# DMESC.net
KiCad netlist of a schematic drawn in Altium Designer
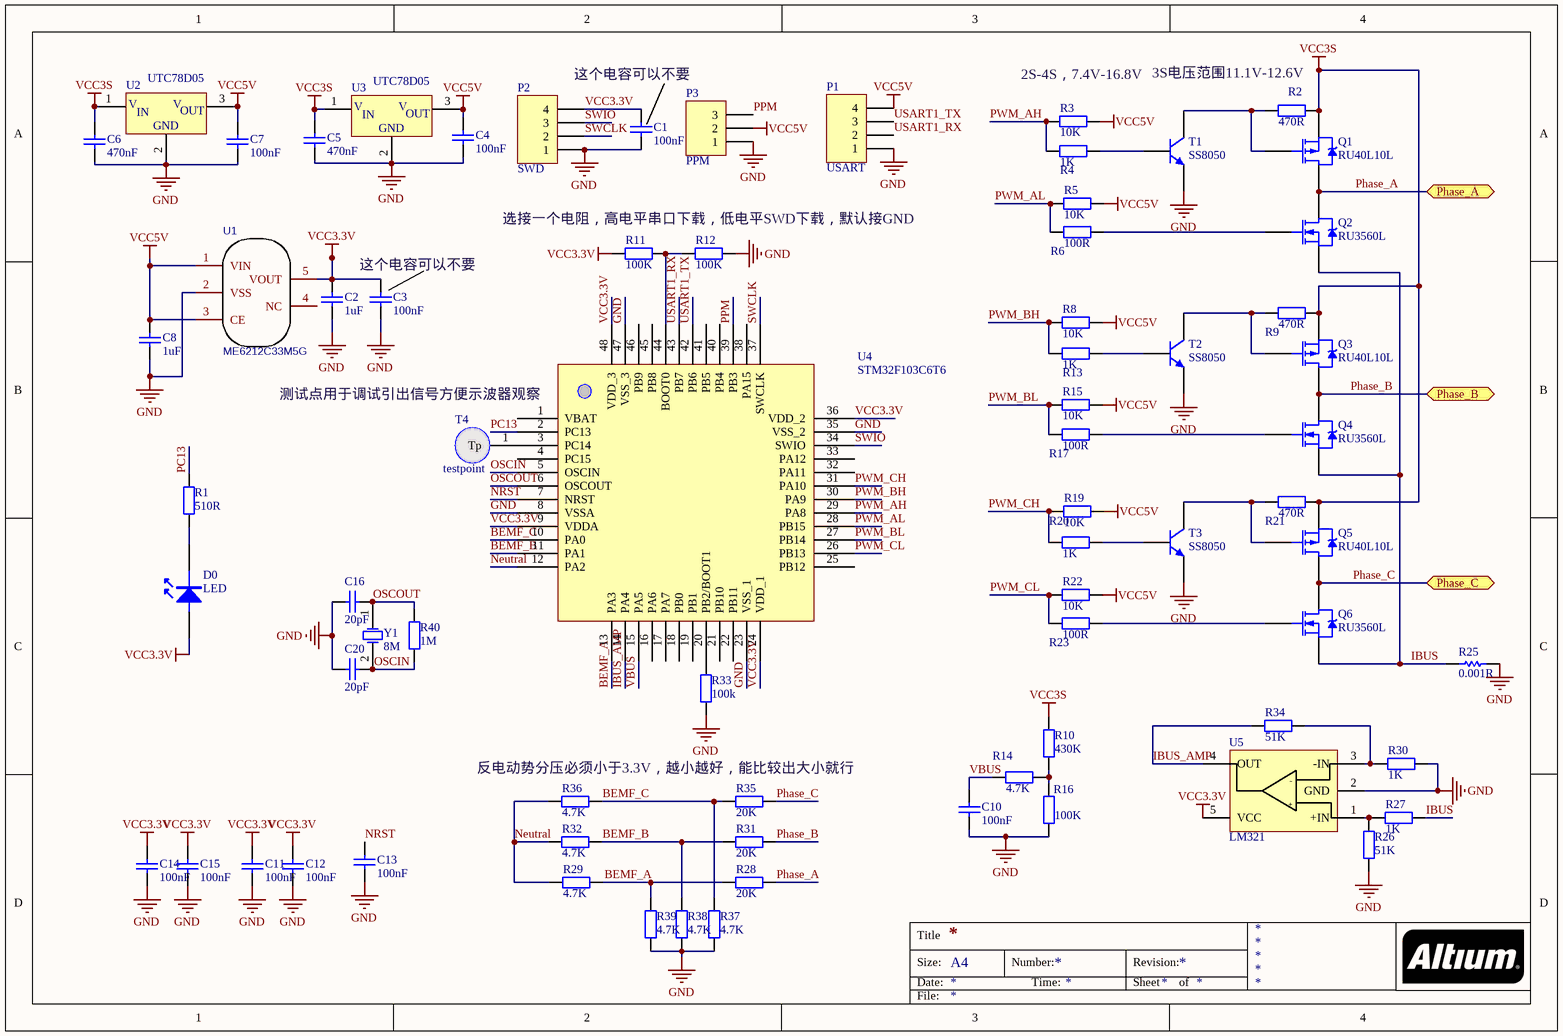
[diagram p0: DMESC.SchDoc]

(export (version "E")
  (design (tool "Eeschema 10.0.6"))
  (components
    (comp (ref "C1")
      (value "100nF")
      (footprint "C0603")
      (description "0.1uF")
      (fields (field (name "PUBLISHER") "Altium Limited"))
      (libsource (lib "Miscellaneous Devices") (part "Cap"))
    )
    (comp (ref "C2")
      (value "1uF")
      (footprint "C0603")
      (fields (field (name "PUBLISHER") "Altium Limited"))
      (libsource (lib "Miscellaneous Devices") (part "Cap"))
    )
    (comp (ref "C3")
      (value "100nF")
      (footprint "C0603")
      (description "0.1uF")
      (fields (field (name "PUBLISHER") "Altium Limited"))
      (libsource (lib "Miscellaneous Devices") (part "Cap"))
    )
    (comp (ref "C4")
      (value "100nF")
      (footprint "C0603")
      (description "贴片电容")
      (fields (field (name "PUBLISHER") "Altium Limited"))
      (libsource (lib "Miscellaneous Devices") (part "Cap"))
    )
    (comp (ref "C5")
      (value "470nF")
      (footprint "C0603")
      (description "贴片电容")
      (fields (field (name "PUBLISHER") "Altium Limited"))
      (libsource (lib "Miscellaneous Devices") (part "Cap"))
    )
    (comp (ref "C6")
      (value "470nF")
      (footprint "C0603")
      (description "贴片电容")
      (fields (field (name "PUBLISHER") "Altium Limited"))
      (libsource (lib "Miscellaneous Devices") (part "Cap"))
    )
    (comp (ref "C7")
      (value "100nF")
      (footprint "C0603")
      (description "贴片电容")
      (fields (field (name "PUBLISHER") "Altium Limited"))
      (libsource (lib "Miscellaneous Devices") (part "Cap"))
    )
    (comp (ref "C8")
      (value "1uF")
      (footprint "C0603")
      (fields (field (name "PUBLISHER") "Altium Limited"))
      (libsource (lib "Miscellaneous Devices") (part "Cap"))
    )
    (comp (ref "C10")
      (value "100nF")
      (footprint "C0603")
      (description "Capacitor")
      (fields (field (name "PUBLISHER") "Altium Limited"))
      (libsource (lib "Miscellaneous Devices") (part "Cap"))
    )
    (comp (ref "C11")
      (value "100nF")
      (footprint "C0603")
      (description "0.1uF")
      (fields (field (name "PUBLISHER") "Altium Limited"))
      (libsource (lib "Miscellaneous Devices") (part "Cap"))
    )
    (comp (ref "C12")
      (value "100nF")
      (footprint "C0603")
      (description "0.1uF")
      (fields (field (name "PUBLISHER") "Altium Limited"))
      (libsource (lib "Miscellaneous Devices") (part "Cap"))
    )
    (comp (ref "C13")
      (value "100nF")
      (footprint "C0603")
      (description "0.1uF")
      (fields (field (name "PUBLISHER") "Altium Limited"))
      (libsource (lib "Miscellaneous Devices") (part "Cap"))
    )
    (comp (ref "C14")
      (value "100nF")
      (footprint "C0603")
      (description "0.1uF")
      (fields (field (name "PUBLISHER") "Altium Limited"))
      (libsource (lib "Miscellaneous Devices") (part "Cap"))
    )
    (comp (ref "C15")
      (value "100nF")
      (footprint "C0603")
      (description "0.1uF")
      (fields (field (name "PUBLISHER") "Altium Limited"))
      (libsource (lib "Miscellaneous Devices") (part "Cap"))
    )
    (comp (ref "C16")
      (value "20pF")
      (footprint "C0603")
      (description "0603")
      (fields (field (name "PUBLISHER") "Altium Limited"))
      (libsource (lib "STM32F103C8T6") (part "Cap"))
    )
    (comp (ref "C20")
      (value "20pF")
      (footprint "C0603")
      (description "0603")
      (fields (field (name "PUBLISHER") "Altium Limited"))
      (libsource (lib "STM32F103C8T6") (part "Cap"))
    )
    (comp (ref "D0") (value "LED") (footprint "0603LED") (libsource (lib "DMESC_1") (part "LED")))
    (comp (ref "P1")
      (value "USART")
      (footprint "HDR1X4")
      (description "Header, 4-Pin")
      (fields (field (name "PUBLISHER") "Altium Limited"))
      (libsource (lib "Miscellaneous Connectors") (part "Header 4"))
    )
    (comp (ref "P2")
      (value "SWD")
      (footprint "HDR1X4")
      (description "Header, 4-Pin")
      (fields (field (name "PUBLISHER") "Altium Limited"))
      (libsource (lib "STM32F103C8T6") (part "Header 4"))
    )
    (comp (ref "P3")
      (value "PPM")
      (footprint "HDR1X3")
      (description "Header, 3-Pin")
      (fields (field (name "PUBLISHER") "Altium Limited"))
      (libsource (lib "Miscellaneous Connectors") (part "Header 3"))
    )
    (comp (ref "Q1")
      (value "RU40L10L")
      (footprint "TO-252")
      (description "PMOSFET")
      (fields
        (field (name "MANUFACTURER") "International Rectifier")
        (field (name "PUBLISHER") "Altium Limited")
      )
      (libsource (lib "DMESC_1") (part "IRFR5305"))
    )
    (comp (ref "Q2")
      (value "RU3560L")
      (footprint "TO-252")
      (description "NMOSFET")
      (fields
        (field (name "MANUFACTURER") "International Rectifier")
        (field (name "PUBLISHER") "Altium Limited")
      )
      (libsource (lib "DMESC_1") (part "IRFR1205"))
    )
    (comp (ref "Q3")
      (value "RU40L10L")
      (footprint "TO-252")
      (description "PMOSFET")
      (fields
        (field (name "MANUFACTURER") "International Rectifier")
        (field (name "PUBLISHER") "Altium Limited")
      )
      (libsource (lib "DMESC_1") (part "IRFR5305"))
    )
    (comp (ref "Q4")
      (value "RU3560L")
      (footprint "TO-252")
      (description "NMOSFET")
      (fields
        (field (name "MANUFACTURER") "International Rectifier")
        (field (name "PUBLISHER") "Altium Limited")
      )
      (libsource (lib "DMESC_1") (part "IRFR1205"))
    )
    (comp (ref "Q5")
      (value "RU40L10L")
      (footprint "TO-252")
      (description "PMOSFET")
      (fields
        (field (name "MANUFACTURER") "International Rectifier")
        (field (name "PUBLISHER") "Altium Limited")
      )
      (libsource (lib "DMESC_1") (part "IRFR5305"))
    )
    (comp (ref "Q6")
      (value "RU3560L")
      (footprint "TO-252")
      (description "NMOSFET")
      (fields
        (field (name "MANUFACTURER") "International Rectifier")
        (field (name "PUBLISHER") "Altium Limited")
      )
      (libsource (lib "DMESC_1") (part "IRFR1205"))
    )
    (comp (ref "R1")
      (value "510R")
      (footprint "R0603")
      (description "0603")
      (fields (field (name "PUBLISHER") "Altium Limited"))
      (libsource (lib "") (part "Res2_3"))
    )
    (comp (ref "R2")
      (value "470R")
      (footprint "R0603")
      (description "Resistor")
      (fields (field (name "PUBLISHER") "Altium Limited"))
      (libsource (lib "") (part "Res2_1"))
    )
    (comp (ref "R3")
      (value "10K")
      (footprint "R0603")
      (description "Resistor")
      (fields (field (name "PUBLISHER") "Altium Limited"))
      (libsource (lib "") (part "Res2_1"))
    )
    (comp (ref "R4")
      (value "1K")
      (footprint "R0603")
      (description "Resistor")
      (fields (field (name "PUBLISHER") "Altium Limited"))
      (libsource (lib "") (part "Res2_1"))
    )
    (comp (ref "R5")
      (value "10K")
      (footprint "R0603")
      (description "Resistor")
      (fields (field (name "PUBLISHER") "Altium Limited"))
      (libsource (lib "") (part "Res2_1"))
    )
    (comp (ref "R6")
      (value "100R")
      (footprint "R0603")
      (description "Resistor")
      (fields (field (name "PUBLISHER") "Altium Limited"))
      (libsource (lib "") (part "Res2_1"))
    )
    (comp (ref "R8")
      (value "10K")
      (footprint "R0603")
      (description "Resistor")
      (fields (field (name "PUBLISHER") "Altium Limited"))
      (libsource (lib "") (part "Res2_1"))
    )
    (comp (ref "R9")
      (value "470R")
      (footprint "R0603")
      (description "Resistor")
      (fields (field (name "PUBLISHER") "Altium Limited"))
      (libsource (lib "") (part "Res2_1"))
    )
    (comp (ref "R10")
      (value "430K")
      (footprint "R0603")
      (description "Resistor")
      (fields (field (name "PUBLISHER") "Altium Limited"))
      (libsource (lib "Miscellaneous Devices") (part "Res2"))
    )
    (comp (ref "R11")
      (value "100K")
      (footprint "R0603")
      (description "0603")
      (fields (field (name "PUBLISHER") "Altium Limited"))
      (libsource (lib "") (part "Res2_2"))
    )
    (comp (ref "R12")
      (value "100K")
      (footprint "R0603")
      (description "0603")
      (fields (field (name "PUBLISHER") "Altium Limited"))
      (libsource (lib "") (part "Res2_1"))
    )
    (comp (ref "R13")
      (value "1K")
      (footprint "R0603")
      (description "Resistor")
      (fields (field (name "PUBLISHER") "Altium Limited"))
      (libsource (lib "") (part "Res2_1"))
    )
    (comp (ref "R14")
      (value "4.7K")
      (footprint "R0603")
      (description "Resistor")
      (fields (field (name "PUBLISHER") "Altium Limited"))
      (libsource (lib "") (part "Res2_1"))
    )
    (comp (ref "R15")
      (value "10K")
      (footprint "R0603")
      (description "Resistor")
      (fields (field (name "PUBLISHER") "Altium Limited"))
      (libsource (lib "") (part "Res2_1"))
    )
    (comp (ref "R16")
      (value "100K")
      (footprint "R0603")
      (description "Resistor")
      (fields (field (name "PUBLISHER") "Altium Limited"))
      (libsource (lib "Miscellaneous Devices") (part "Res2"))
    )
    (comp (ref "R17")
      (value "100R")
      (footprint "R0603")
      (description "Resistor")
      (fields (field (name "PUBLISHER") "Altium Limited"))
      (libsource (lib "") (part "Res2_1"))
    )
    (comp (ref "R19")
      (value "10K")
      (footprint "R0603")
      (description "Resistor")
      (fields (field (name "PUBLISHER") "Altium Limited"))
      (libsource (lib "") (part "Res2_1"))
    )
    (comp (ref "R20")
      (value "1K")
      (footprint "R0603")
      (description "Resistor")
      (fields (field (name "PUBLISHER") "Altium Limited"))
      (libsource (lib "") (part "Res2_1"))
    )
    (comp (ref "R21")
      (value "470R")
      (footprint "R0603")
      (description "Resistor")
      (fields (field (name "PUBLISHER") "Altium Limited"))
      (libsource (lib "") (part "Res2_1"))
    )
    (comp (ref "R22")
      (value "10K")
      (footprint "R0603")
      (description "Resistor")
      (fields (field (name "PUBLISHER") "Altium Limited"))
      (libsource (lib "") (part "Res2_1"))
    )
    (comp (ref "R23")
      (value "100R")
      (footprint "R0603")
      (description "Resistor")
      (fields (field (name "PUBLISHER") "Altium Limited"))
      (libsource (lib "") (part "Res2_1"))
    )
    (comp (ref "R25")
      (value "0.001R")
      (footprint "2512")
      (description "11毫欧采样电阻")
      (fields (field (name "PUBLISHER") "Altium Limited"))
      (libsource (lib "Miscellaneous Devices") (part "Res1"))
    )
    (comp (ref "R26")
      (value "51K")
      (footprint "R0603")
      (description "Resistor")
      (fields (field (name "PUBLISHER") "Altium Limited"))
      (libsource (lib "") (part "Res2_3"))
    )
    (comp (ref "R27")
      (value "1K")
      (footprint "R0603")
      (description "Resistor")
      (fields (field (name "PUBLISHER") "Altium Limited"))
      (libsource (lib "") (part "Res2_2"))
    )
    (comp (ref "R28")
      (value "20K")
      (footprint "R0603")
      (description "Resistor")
      (fields (field (name "PUBLISHER") "Altium Limited"))
      (libsource (lib "") (part "Res2_2"))
    )
    (comp (ref "R29")
      (value "4.7K")
      (footprint "R0603")
      (description "Resistor")
      (fields (field (name "PUBLISHER") "Altium Limited"))
      (libsource (lib "") (part "Res2_2"))
    )
    (comp (ref "R30")
      (value "1K")
      (footprint "R0603")
      (description "Resistor")
      (fields (field (name "PUBLISHER") "Altium Limited"))
      (libsource (lib "") (part "Res2_2"))
    )
    (comp (ref "R31")
      (value "20K")
      (footprint "R0603")
      (description "Resistor")
      (fields (field (name "PUBLISHER") "Altium Limited"))
      (libsource (lib "") (part "Res2_2"))
    )
    (comp (ref "R32")
      (value "4.7K")
      (footprint "R0603")
      (description "Resistor")
      (fields (field (name "PUBLISHER") "Altium Limited"))
      (libsource (lib "") (part "Res2_2"))
    )
    (comp (ref "R33")
      (value "100k")
      (footprint "R0603")
      (description "0603")
      (fields (field (name "PUBLISHER") "Altium Limited"))
      (libsource (lib "STM32F103C8T6") (part "Res2"))
    )
    (comp (ref "R34")
      (value "51K")
      (footprint "R0603")
      (description "Resistor")
      (fields (field (name "PUBLISHER") "Altium Limited"))
      (libsource (lib "") (part "Res2_2"))
    )
    (comp (ref "R35")
      (value "20K")
      (footprint "R0603")
      (description "Resistor")
      (fields (field (name "PUBLISHER") "Altium Limited"))
      (libsource (lib "") (part "Res2_2"))
    )
    (comp (ref "R36")
      (value "4.7K")
      (footprint "R0603")
      (description "Resistor")
      (fields (field (name "PUBLISHER") "Altium Limited"))
      (libsource (lib "") (part "Res2_2"))
    )
    (comp (ref "R37")
      (value "4.7K")
      (footprint "R0603")
      (description "Resistor")
      (fields (field (name "PUBLISHER") "Altium Limited"))
      (libsource (lib "Miscellaneous Devices") (part "Res2"))
    )
    (comp (ref "R38")
      (value "4.7K")
      (footprint "R0603")
      (description "Resistor")
      (fields (field (name "PUBLISHER") "Altium Limited"))
      (libsource (lib "Miscellaneous Devices") (part "Res2"))
    )
    (comp (ref "R39")
      (value "4.7K")
      (footprint "R0603")
      (description "Resistor")
      (fields (field (name "PUBLISHER") "Altium Limited"))
      (libsource (lib "Miscellaneous Devices") (part "Res2"))
    )
    (comp (ref "R40")
      (value "1M")
      (footprint "R0603")
      (description "0603")
      (fields (field (name "PUBLISHER") "Altium Limited"))
      (libsource (lib "STM32F103C8T6") (part "Res2"))
    )
    (comp (ref "T1")
      (value "SS8050")
      (footprint "SOT-23")
      (description "NPN三极管")
      (libsource (lib "DMESC_1") (part "2N3904"))
    )
    (comp (ref "T2")
      (value "SS8050")
      (footprint "SOT-23")
      (description "NPN三极管")
      (libsource (lib "DMESC_1") (part "2N3904"))
    )
    (comp (ref "T3")
      (value "SS8050")
      (footprint "SOT-23")
      (description "NPN三极管")
      (libsource (lib "DMESC_1") (part "2N3904"))
    )
    (comp (ref "T4")
      (value "testpoint")
      (footprint "testpoint")
      (description "测试点用焊盘代替，不需要元器件")
      (libsource (lib "neckcheck3.0") (part "testpoint"))
    )
    (comp (ref "U1")
      (value "ME6212C33M5G")
      (footprint "ME6212C33M5G")
      (fields (field (name "BOM_SUPPLIER PART") "C81233"))
      (libsource (lib "Sheet_1_2021-08-16") (part "ME6212C33M5G"))
    )
    (comp (ref "U2")
      (value "UTC78D05")
      (footprint "TO-252")
      (description "线性稳压")
      (libsource (lib "BLDC-M8") (part "78L05"))
    )
    (comp (ref "U3")
      (value "UTC78D05")
      (footprint "TO-252")
      (description "线性稳压")
      (libsource (lib "BLDC-M8") (part "78L05"))
    )
    (comp (ref "U4")
      (value "STM32F103C6T6")
      (footprint "STM32F103C6T6")
      (libsource (lib "STM32F103C8T6") (part "STM32F103C8T6"))
    )
    (comp (ref "U5")
      (value "LM321")
      (footprint "SOT23-5")
      (description "单路运放")
      (libsource (lib "DMESC") (part "LM321"))
    )
    (comp (ref "Y1")
      (value "8M")
      (footprint "3225")
      (description "Crystal Oscillator")
      (fields (field (name "PUBLISHER") "Altium Limited"))
      (libsource (lib "STM32F103C8T6") (part "XTAL"))
    )
  )
  (nets
    (net (code "1") (name "/BEMF_A") (class "Default")
      (node (ref "R28") (pin "2") (pinfunction "2_2") (pintype "passive"))
      (node (ref "R29") (pin "1") (pinfunction "1_1") (pintype "passive"))
      (node (ref "R39") (pin "2") (pinfunction "2_2") (pintype "passive"))
      (node (ref "U4") (pin "13") (pinfunction "PA3_13") (pintype "passive"))
    )
    (net (code "2") (name "/BEMF_B") (class "Default")
      (node (ref "R31") (pin "2") (pinfunction "2_2") (pintype "passive"))
      (node (ref "R32") (pin "1") (pinfunction "1_1") (pintype "passive"))
      (node (ref "R38") (pin "2") (pinfunction "2_2") (pintype "passive"))
      (node (ref "U4") (pin "11") (pinfunction "PA1_11") (pintype "passive"))
    )
    (net (code "3") (name "/BEMF_C") (class "Default")
      (node (ref "R35") (pin "2") (pinfunction "2_2") (pintype "passive"))
      (node (ref "R36") (pin "1") (pinfunction "1_1") (pintype "passive"))
      (node (ref "R37") (pin "2") (pinfunction "2_2") (pintype "passive"))
      (node (ref "U4") (pin "10") (pinfunction "PA0_10") (pintype "passive"))
    )
    (net (code "4") (name "/IBUS") (class "Default")
      (node (ref "Q2") (pin "3") (pinfunction "S_3") (pintype "passive"))
      (node (ref "Q4") (pin "3") (pinfunction "S_3") (pintype "passive"))
      (node (ref "Q6") (pin "3") (pinfunction "S_3") (pintype "passive"))
      (node (ref "R25") (pin "1") (pinfunction "1_1") (pintype "passive"))
      (node (ref "R27") (pin "1") (pinfunction "1_1") (pintype "passive"))
    )
    (net (code "5") (name "/IBUS_AMP") (class "Default")
      (node (ref "R34") (pin "2") (pinfunction "2_2") (pintype "passive"))
      (node (ref "U4") (pin "14") (pinfunction "PA4_14") (pintype "passive"))
      (node (ref "U5") (pin "4") (pinfunction "OUT_4") (pintype "passive"))
    )
    (net (code "6") (name "/NRST") (class "Default")
      (node (ref "C13") (pin "1") (pinfunction "1_1") (pintype "passive"))
      (node (ref "U4") (pin "7") (pinfunction "NRST_7") (pintype "passive"))
    )
    (net (code "7") (name "/Neutral") (class "Default")
      (node (ref "R29") (pin "2") (pinfunction "2_2") (pintype "passive"))
      (node (ref "R32") (pin "2") (pinfunction "2_2") (pintype "passive"))
      (node (ref "R36") (pin "2") (pinfunction "2_2") (pintype "passive"))
      (node (ref "U4") (pin "12") (pinfunction "PA2_12") (pintype "passive"))
    )
    (net (code "8") (name "/OSCIN") (class "Default")
      (node (ref "C20") (pin "2") (pinfunction "2_2") (pintype "passive"))
      (node (ref "R40") (pin "1") (pinfunction "1_1") (pintype "passive"))
      (node (ref "U4") (pin "5") (pinfunction "OSCIN_5") (pintype "passive"))
      (node (ref "Y1") (pin "2") (pinfunction "2_2") (pintype "passive"))
    )
    (net (code "9") (name "/OSCOUT") (class "Default")
      (node (ref "C16") (pin "2") (pinfunction "2_2") (pintype "passive"))
      (node (ref "R40") (pin "2") (pinfunction "2_2") (pintype "passive"))
      (node (ref "U4") (pin "6") (pinfunction "OSCOUT_6") (pintype "passive"))
      (node (ref "Y1") (pin "1") (pinfunction "1_1") (pintype "passive"))
    )
    (net (code "10") (name "/PC13") (class "Default")
      (node (ref "R1") (pin "1") (pinfunction "1_1") (pintype "passive"))
      (node (ref "U4") (pin "2") (pinfunction "PC13_2") (pintype "passive"))
    )
    (net (code "11") (name "/PPM") (class "Default")
      (node (ref "P3") (pin "3") (pinfunction "3_3") (pintype "passive"))
      (node (ref "U4") (pin "39") (pinfunction "PB3_39") (pintype "passive"))
    )
    (net (code "12") (name "/PWM_AH") (class "Default")
      (node (ref "R3") (pin "1") (pinfunction "1_1") (pintype "passive"))
      (node (ref "R4") (pin "1") (pinfunction "1_1") (pintype "passive"))
      (node (ref "U4") (pin "29") (pinfunction "PA8_29") (pintype "passive"))
    )
    (net (code "13") (name "/PWM_AL") (class "Default")
      (node (ref "R5") (pin "1") (pinfunction "1_1") (pintype "passive"))
      (node (ref "R6") (pin "1") (pinfunction "1_1") (pintype "passive"))
      (node (ref "U4") (pin "28") (pinfunction "PB15_28") (pintype "passive"))
    )
    (net (code "14") (name "/PWM_BH") (class "Default")
      (node (ref "R13") (pin "1") (pinfunction "1_1") (pintype "passive"))
      (node (ref "R8") (pin "1") (pinfunction "1_1") (pintype "passive"))
      (node (ref "U4") (pin "30") (pinfunction "PA9_30") (pintype "passive"))
    )
    (net (code "15") (name "/PWM_BL") (class "Default")
      (node (ref "R15") (pin "1") (pinfunction "1_1") (pintype "passive"))
      (node (ref "R17") (pin "1") (pinfunction "1_1") (pintype "passive"))
      (node (ref "U4") (pin "27") (pinfunction "PB14_27") (pintype "passive"))
    )
    (net (code "16") (name "/PWM_CH") (class "Default")
      (node (ref "R19") (pin "1") (pinfunction "1_1") (pintype "passive"))
      (node (ref "R20") (pin "1") (pinfunction "1_1") (pintype "passive"))
      (node (ref "U4") (pin "31") (pinfunction "PA10_31") (pintype "passive"))
    )
    (net (code "17") (name "/PWM_CL") (class "Default")
      (node (ref "R22") (pin "1") (pinfunction "1_1") (pintype "passive"))
      (node (ref "R23") (pin "1") (pinfunction "1_1") (pintype "passive"))
      (node (ref "U4") (pin "26") (pinfunction "PB13_26") (pintype "passive"))
    )
    (net (code "18") (name "/Phase_A") (class "Default")
      (node (ref "Q1") (pin "2") (pinfunction "D_2") (pintype "passive"))
      (node (ref "Q2") (pin "2") (pinfunction "D_2") (pintype "passive"))
      (node (ref "R28") (pin "1") (pinfunction "1_1") (pintype "passive"))
    )
    (net (code "19") (name "/Phase_B") (class "Default")
      (node (ref "Q3") (pin "2") (pinfunction "D_2") (pintype "passive"))
      (node (ref "Q4") (pin "2") (pinfunction "D_2") (pintype "passive"))
      (node (ref "R31") (pin "1") (pinfunction "1_1") (pintype "passive"))
    )
    (net (code "20") (name "/Phase_C") (class "Default")
      (node (ref "Q5") (pin "2") (pinfunction "D_2") (pintype "passive"))
      (node (ref "Q6") (pin "2") (pinfunction "D_2") (pintype "passive"))
      (node (ref "R35") (pin "1") (pinfunction "1_1") (pintype "passive"))
    )
    (net (code "21") (name "/SWCLK") (class "Default")
      (node (ref "P2") (pin "2") (pinfunction "2_2") (pintype "passive"))
      (node (ref "U4") (pin "37") (pinfunction "SWCLK_37") (pintype "passive"))
    )
    (net (code "22") (name "/SWIO") (class "Default")
      (node (ref "P2") (pin "3") (pinfunction "3_3") (pintype "passive"))
      (node (ref "U4") (pin "34") (pinfunction "SWIO_34") (pintype "passive"))
    )
    (net (code "23") (name "/USART1_RX") (class "Default")
      (node (ref "P1") (pin "2") (pinfunction "2_2") (pintype "passive"))
      (node (ref "U4") (pin "43") (pinfunction "PB7_43") (pintype "passive"))
    )
    (net (code "24") (name "/USART1_TX") (class "Default")
      (node (ref "P1") (pin "3") (pinfunction "3_3") (pintype "passive"))
      (node (ref "U4") (pin "42") (pinfunction "PB6_42") (pintype "passive"))
    )
    (net (code "25") (name "/VBUS") (class "Default")
      (node (ref "C10") (pin "2") (pinfunction "2_2") (pintype "passive"))
      (node (ref "R14") (pin "1") (pinfunction "1_1") (pintype "passive"))
      (node (ref "U4") (pin "15") (pinfunction "PA5_15") (pintype "passive"))
    )
    (net (code "26") (name "GND") (class "Default")
      (node (ref "C1") (pin "1") (pinfunction "1_1") (pintype "passive"))
      (node (ref "C10") (pin "1") (pinfunction "1_1") (pintype "passive"))
      (node (ref "C11") (pin "1") (pinfunction "1_1") (pintype "passive"))
      (node (ref "C12") (pin "1") (pinfunction "1_1") (pintype "passive"))
      (node (ref "C13") (pin "2") (pinfunction "2_2") (pintype "passive"))
      (node (ref "C14") (pin "1") (pinfunction "1_1") (pintype "passive"))
      (node (ref "C15") (pin "1") (pinfunction "1_1") (pintype "passive"))
      (node (ref "C16") (pin "1") (pinfunction "1_1") (pintype "passive"))
      (node (ref "C2") (pin "1") (pinfunction "1_1") (pintype "passive"))
      (node (ref "C20") (pin "1") (pinfunction "1_1") (pintype "passive"))
      (node (ref "C3") (pin "1") (pinfunction "1_1") (pintype "passive"))
      (node (ref "C4") (pin "1") (pinfunction "1_1") (pintype "passive"))
      (node (ref "C5") (pin "1") (pinfunction "1_1") (pintype "passive"))
      (node (ref "C6") (pin "1") (pinfunction "1_1") (pintype "passive"))
      (node (ref "C7") (pin "1") (pinfunction "1_1") (pintype "passive"))
      (node (ref "C8") (pin "1") (pinfunction "1_1") (pintype "passive"))
      (node (ref "P1") (pin "1") (pinfunction "1_1") (pintype "passive"))
      (node (ref "P2") (pin "1") (pinfunction "1_1") (pintype "passive"))
      (node (ref "P3") (pin "1") (pinfunction "1_1") (pintype "passive"))
      (node (ref "R12") (pin "2") (pinfunction "2_2") (pintype "passive"))
      (node (ref "R16") (pin "1") (pinfunction "1_1") (pintype "passive"))
      (node (ref "R25") (pin "2") (pinfunction "2_2") (pintype "passive"))
      (node (ref "R26") (pin "2") (pinfunction "2_2") (pintype "passive"))
      (node (ref "R30") (pin "1") (pinfunction "1_1") (pintype "passive"))
      (node (ref "R33") (pin "1") (pinfunction "1_1") (pintype "passive"))
      (node (ref "R37") (pin "1") (pinfunction "1_1") (pintype "passive"))
      (node (ref "R38") (pin "1") (pinfunction "1_1") (pintype "passive"))
      (node (ref "R39") (pin "1") (pinfunction "1_1") (pintype "passive"))
      (node (ref "T1") (pin "2") (pinfunction "E_2") (pintype "passive"))
      (node (ref "T2") (pin "2") (pinfunction "E_2") (pintype "passive"))
      (node (ref "T3") (pin "2") (pinfunction "E_2") (pintype "passive"))
      (node (ref "U1") (pin "2") (pinfunction "VSS_2") (pintype "passive"))
      (node (ref "U2") (pin "2") (pinfunction "GND_2") (pintype "passive"))
      (node (ref "U3") (pin "2") (pinfunction "GND_2") (pintype "passive"))
      (node (ref "U4") (pin "23") (pinfunction "VSS_1_23") (pintype "passive"))
      (node (ref "U4") (pin "35") (pinfunction "VSS_2_35") (pintype "passive"))
      (node (ref "U4") (pin "47") (pinfunction "VSS_3_47") (pintype "passive"))
      (node (ref "U4") (pin "8") (pinfunction "VSSA_8") (pintype "passive"))
      (node (ref "U5") (pin "2") (pinfunction "GND_2") (pintype "passive"))
    )
    (net (code "27") (name "Net-(D0-Pad2)") (class "Default")
      (node (ref "D0") (pin "2") (pinfunction "2_2") (pintype "passive"))
      (node (ref "R1") (pin "2") (pinfunction "2_2") (pintype "passive"))
    )
    (net (code "28") (name "Net-(Q1-G)") (class "Default")
      (node (ref "Q1") (pin "1") (pinfunction "G_1") (pintype "passive"))
      (node (ref "R2") (pin "1") (pinfunction "1_1") (pintype "passive"))
      (node (ref "T1") (pin "3") (pinfunction "C_3") (pintype "passive"))
    )
    (net (code "29") (name "Net-(Q2-G)") (class "Default")
      (node (ref "Q2") (pin "1") (pinfunction "G_1") (pintype "passive"))
      (node (ref "R6") (pin "2") (pinfunction "2_2") (pintype "passive"))
    )
    (net (code "30") (name "Net-(Q3-G)") (class "Default")
      (node (ref "Q3") (pin "1") (pinfunction "G_1") (pintype "passive"))
      (node (ref "R9") (pin "1") (pinfunction "1_1") (pintype "passive"))
      (node (ref "T2") (pin "3") (pinfunction "C_3") (pintype "passive"))
    )
    (net (code "31") (name "Net-(Q4-G)") (class "Default")
      (node (ref "Q4") (pin "1") (pinfunction "G_1") (pintype "passive"))
      (node (ref "R17") (pin "2") (pinfunction "2_2") (pintype "passive"))
    )
    (net (code "32") (name "Net-(Q5-G)") (class "Default")
      (node (ref "Q5") (pin "1") (pinfunction "G_1") (pintype "passive"))
      (node (ref "R21") (pin "1") (pinfunction "1_1") (pintype "passive"))
      (node (ref "T3") (pin "3") (pinfunction "C_3") (pintype "passive"))
    )
    (net (code "33") (name "Net-(Q6-G)") (class "Default")
      (node (ref "Q6") (pin "1") (pinfunction "G_1") (pintype "passive"))
      (node (ref "R23") (pin "2") (pinfunction "2_2") (pintype "passive"))
    )
    (net (code "34") (name "Net-(R10-Pad1)") (class "Default")
      (node (ref "R10") (pin "1") (pinfunction "1_1") (pintype "passive"))
      (node (ref "R14") (pin "2") (pinfunction "2_2") (pintype "passive"))
      (node (ref "R16") (pin "2") (pinfunction "2_2") (pintype "passive"))
    )
    (net (code "35") (name "Net-(T1-B)") (class "Default")
      (node (ref "R4") (pin "2") (pinfunction "2_2") (pintype "passive"))
      (node (ref "T1") (pin "1") (pinfunction "B_1") (pintype "passive"))
    )
    (net (code "36") (name "Net-(T2-B)") (class "Default")
      (node (ref "R13") (pin "2") (pinfunction "2_2") (pintype "passive"))
      (node (ref "T2") (pin "1") (pinfunction "B_1") (pintype "passive"))
    )
    (net (code "37") (name "Net-(T3-B)") (class "Default")
      (node (ref "R20") (pin "2") (pinfunction "2_2") (pintype "passive"))
      (node (ref "T3") (pin "1") (pinfunction "B_1") (pintype "passive"))
    )
    (net (code "38") (name "Net-(T4-Tp)") (class "Default")
      (node (ref "T4") (pin "1") (pinfunction "Tp_1") (pintype "passive"))
      (node (ref "U4") (pin "3") (pinfunction "PC14_3") (pintype "passive"))
    )
    (net (code "39") (name "Net-(U4-BOOT0)") (class "Default")
      (node (ref "R11") (pin "1") (pinfunction "1_1") (pintype "passive"))
      (node (ref "R12") (pin "1") (pinfunction "1_1") (pintype "passive"))
      (node (ref "U4") (pin "44") (pinfunction "BOOT0_44") (pintype "passive"))
    )
    (net (code "40") (name "Net-(U4-PB2{slash}BOOT1)") (class "Default")
      (node (ref "R33") (pin "2") (pinfunction "2_2") (pintype "passive"))
      (node (ref "U4") (pin "20") (pinfunction "PB2/BOOT1_20") (pintype "passive"))
    )
    (net (code "41") (name "Net-(U5-+IN)") (class "Default")
      (node (ref "R26") (pin "1") (pinfunction "1_1") (pintype "passive"))
      (node (ref "R27") (pin "2") (pinfunction "2_2") (pintype "passive"))
      (node (ref "U5") (pin "1") (pinfunction "+IN_1") (pintype "passive"))
    )
    (net (code "42") (name "Net-(U5--IN)") (class "Default")
      (node (ref "R30") (pin "2") (pinfunction "2_2") (pintype "passive"))
      (node (ref "R34") (pin "1") (pinfunction "1_1") (pintype "passive"))
      (node (ref "U5") (pin "3") (pinfunction "-IN_3") (pintype "passive"))
    )
    (net (code "43") (name "VCC3.3V") (class "Default")
      (node (ref "C1") (pin "2") (pinfunction "2_2") (pintype "passive"))
      (node (ref "C11") (pin "2") (pinfunction "2_2") (pintype "passive"))
      (node (ref "C12") (pin "2") (pinfunction "2_2") (pintype "passive"))
      (node (ref "C14") (pin "2") (pinfunction "2_2") (pintype "passive"))
      (node (ref "C15") (pin "2") (pinfunction "2_2") (pintype "passive"))
      (node (ref "C2") (pin "2") (pinfunction "2_2") (pintype "passive"))
      (node (ref "C3") (pin "2") (pinfunction "2_2") (pintype "passive"))
      (node (ref "D0") (pin "1") (pinfunction "1_1") (pintype "passive"))
      (node (ref "P2") (pin "4") (pinfunction "4_4") (pintype "passive"))
      (node (ref "R11") (pin "2") (pinfunction "2_2") (pintype "passive"))
      (node (ref "U1") (pin "5") (pinfunction "VOUT_5") (pintype "passive"))
      (node (ref "U4") (pin "24") (pinfunction "VDD_1_24") (pintype "passive"))
      (node (ref "U4") (pin "36") (pinfunction "VDD_2_36") (pintype "passive"))
      (node (ref "U4") (pin "48") (pinfunction "VDD_3_48") (pintype "passive"))
      (node (ref "U4") (pin "9") (pinfunction "VDDA_9") (pintype "passive"))
      (node (ref "U5") (pin "5") (pinfunction "VCC_5") (pintype "passive"))
    )
    (net (code "44") (name "VCC3S") (class "Default")
      (node (ref "C5") (pin "2") (pinfunction "2_2") (pintype "passive"))
      (node (ref "C6") (pin "2") (pinfunction "2_2") (pintype "passive"))
      (node (ref "Q1") (pin "3") (pinfunction "S_3") (pintype "passive"))
      (node (ref "Q3") (pin "3") (pinfunction "S_3") (pintype "passive"))
      (node (ref "Q5") (pin "3") (pinfunction "S_3") (pintype "passive"))
      (node (ref "R10") (pin "2") (pinfunction "2_2") (pintype "passive"))
      (node (ref "R2") (pin "2") (pinfunction "2_2") (pintype "passive"))
      (node (ref "R21") (pin "2") (pinfunction "2_2") (pintype "passive"))
      (node (ref "R9") (pin "2") (pinfunction "2_2") (pintype "passive"))
      (node (ref "U2") (pin "1") (pinfunction "VIN_1") (pintype "passive"))
      (node (ref "U3") (pin "1") (pinfunction "VIN_1") (pintype "passive"))
    )
    (net (code "45") (name "VCC5V") (class "Default")
      (node (ref "C4") (pin "2") (pinfunction "2_2") (pintype "passive"))
      (node (ref "C7") (pin "2") (pinfunction "2_2") (pintype "passive"))
      (node (ref "C8") (pin "2") (pinfunction "2_2") (pintype "passive"))
      (node (ref "P1") (pin "4") (pinfunction "4_4") (pintype "passive"))
      (node (ref "P3") (pin "2") (pinfunction "2_2") (pintype "passive"))
      (node (ref "R15") (pin "2") (pinfunction "2_2") (pintype "passive"))
      (node (ref "R19") (pin "2") (pinfunction "2_2") (pintype "passive"))
      (node (ref "R22") (pin "2") (pinfunction "2_2") (pintype "passive"))
      (node (ref "R3") (pin "2") (pinfunction "2_2") (pintype "passive"))
      (node (ref "R5") (pin "2") (pinfunction "2_2") (pintype "passive"))
      (node (ref "R8") (pin "2") (pinfunction "2_2") (pintype "passive"))
      (node (ref "U1") (pin "1") (pinfunction "VIN_1") (pintype "passive"))
      (node (ref "U1") (pin "3") (pinfunction "CE_3") (pintype "passive"))
      (node (ref "U2") (pin "3") (pinfunction "VOUT_3") (pintype "passive"))
      (node (ref "U3") (pin "3") (pinfunction "VOUT_3") (pintype "passive"))
    )
    (net (code "46") (name "unconnected-(U1-NC-Pad4)") (class "Default")
      (node (ref "U1") (pin "4") (pinfunction "NC_4") (pintype "passive"))
    )
    (net (code "47") (name "unconnected-(U4-PA6-Pad16)") (class "Default")
      (node (ref "U4") (pin "16") (pinfunction "PA6_16") (pintype "passive"))
    )
    (net (code "48") (name "unconnected-(U4-PA7-Pad17)") (class "Default")
      (node (ref "U4") (pin "17") (pinfunction "PA7_17") (pintype "passive"))
    )
    (net (code "49") (name "unconnected-(U4-PA11-Pad32)") (class "Default")
      (node (ref "U4") (pin "32") (pinfunction "PA11_32") (pintype "passive"))
    )
    (net (code "50") (name "unconnected-(U4-PA12-Pad33)") (class "Default")
      (node (ref "U4") (pin "33") (pinfunction "PA12_33") (pintype "passive"))
    )
    (net (code "51") (name "unconnected-(U4-PA15-Pad38)") (class "Default")
      (node (ref "U4") (pin "38") (pinfunction "PA15_38") (pintype "passive"))
    )
    (net (code "52") (name "unconnected-(U4-PB0-Pad18)") (class "Default")
      (node (ref "U4") (pin "18") (pinfunction "PB0_18") (pintype "passive"))
    )
    (net (code "53") (name "unconnected-(U4-PB1-Pad19)") (class "Default")
      (node (ref "U4") (pin "19") (pinfunction "PB1_19") (pintype "passive"))
    )
    (net (code "54") (name "unconnected-(U4-PB4-Pad40)") (class "Default")
      (node (ref "U4") (pin "40") (pinfunction "PB4_40") (pintype "passive"))
    )
    (net (code "55") (name "unconnected-(U4-PB5-Pad41)") (class "Default")
      (node (ref "U4") (pin "41") (pinfunction "PB5_41") (pintype "passive"))
    )
    (net (code "56") (name "unconnected-(U4-PB8-Pad45)") (class "Default")
      (node (ref "U4") (pin "45") (pinfunction "PB8_45") (pintype "passive"))
    )
    (net (code "57") (name "unconnected-(U4-PB9-Pad46)") (class "Default")
      (node (ref "U4") (pin "46") (pinfunction "PB9_46") (pintype "passive"))
    )
    (net (code "58") (name "unconnected-(U4-PB10-Pad21)") (class "Default")
      (node (ref "U4") (pin "21") (pinfunction "PB10_21") (pintype "passive"))
    )
    (net (code "59") (name "unconnected-(U4-PB11-Pad22)") (class "Default")
      (node (ref "U4") (pin "22") (pinfunction "PB11_22") (pintype "passive"))
    )
    (net (code "60") (name "unconnected-(U4-PB12-Pad25)") (class "Default")
      (node (ref "U4") (pin "25") (pinfunction "PB12_25") (pintype "passive"))
    )
    (net (code "61") (name "unconnected-(U4-PC15-Pad4)") (class "Default")
      (node (ref "U4") (pin "4") (pinfunction "PC15_4") (pintype "passive"))
    )
    (net (code "62") (name "unconnected-(U4-VBAT-Pad1)") (class "Default")
      (node (ref "U4") (pin "1") (pinfunction "VBAT_1") (pintype "passive"))
    )
  )
)
